# Relay_module.net
KiCad netlist of a schematic drawn in Altium Designer
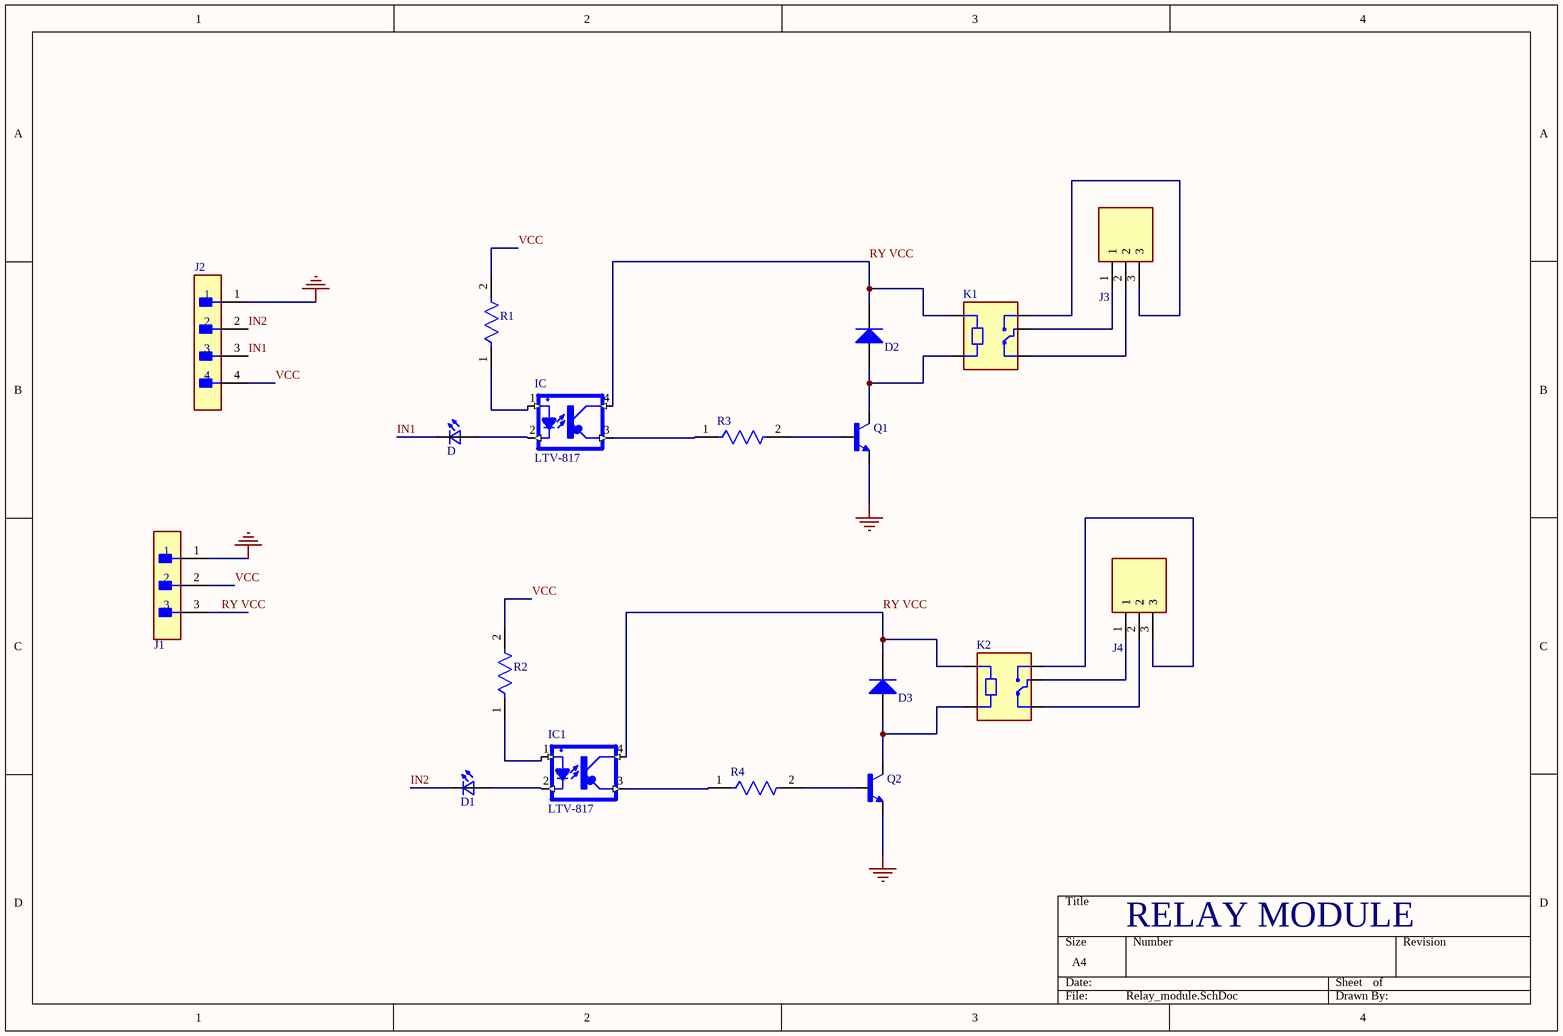
[diagram p0: Relay_module.SchDoc]

(export (version "E")
  (design (tool "Eeschema 10.0.6"))
  (components
    (comp (ref "D")
      (value "LTST-C193TBKT-5A")
      (footprint "0603")
      (description "Blue 470nm LED Indication - Discrete 2.8V 0603 _1608 Metric_")
      (fields (field (name "DIGI-KEY_PART_NUMBER") "160-1827-1-ND") (field (name "MF") "Lite-On Inc."))
      (libsource (lib "led") (part "LTST-C193TBKT-5A"))
    )
    (comp (ref "D1")
      (value "LTST-C193TBKT-5A")
      (footprint "0603")
      (description "Blue 470nm LED Indication - Discrete 2.8V 0603 _1608 Metric_")
      (fields (field (name "DIGI-KEY_PART_NUMBER") "160-1827-1-ND") (field (name "MF") "Lite-On Inc."))
      (libsource (lib "led") (part "LTST-C193TBKT-5A"))
    )
    (comp (ref "D2")
      (value "1N4003-T")
      (footprint "DIOD-DO-41-P-2_V")
      (description "1.0 A Rectifier, 15 pF, 200 V, -65 to 150 degC, 2-Pin DO-41 Plastic, RoHS, Tape and Reel")
      (fields (field (name "MANUFACTURER") "Diodes Inc"))
      (libsource (lib "Altium Content Vault") (part "DIOD-D-A1K2-2"))
    )
    (comp (ref "D3")
      (value "1N4003-T")
      (footprint "DIOD-DO-41-P-2_V")
      (description "1.0 A Rectifier, 15 pF, 200 V, -65 to 150 degC, 2-Pin DO-41 Plastic, RoHS, Tape and Reel")
      (fields (field (name "MANUFACTURER") "Diodes Inc"))
      (libsource (lib "Altium Content Vault") (part "DIOD-D-A1K2-2"))
    )
    (comp (ref "IC")
      (value "LTV-817")
      (footprint "DIP-4")
      (description "Optoisolator Transistor Output 5000Vrms 1 Channel 4-SMD")
      (fields (field (name "MF") "Lite-On Electronics"))
      (libsource (lib "SnapEDAsch") (part "LTV-817"))
    )
    (comp (ref "IC1")
      (value "LTV-817")
      (footprint "DIP-4")
      (description "Optoisolator Transistor Output 5000Vrms 1 Channel 4-SMD")
      (fields (field (name "MF") "Lite-On Electronics"))
      (libsource (lib "SnapEDAsch") (part "LTV-817"))
    )
    (comp (ref "J1")
      (value "22-05-3031")
      (footprint "FP-22-05-3031-MFG")
      (description "CONN HEADER R/A 3POS 2.54MM")
      (libsource (lib "Altium Content Vault") (part "0d3f023dd272f625e17a2be33dea85f"))
    )
    (comp (ref "J2")
      (value "22-05-3041")
      (footprint "FP-22-05-3041-MFG")
      (description "Connector Header Through Hole, Right Angle 4 position 0.100\" (2.54mm)")
      (fields (field (name "OCTOPART") "https://octopart.com/22-05-3041-molex-2579"))
      (libsource (lib "Altium Content Vault") (part "299a8cea1bdcbc3624fe62c390fa72c"))
    )
    (comp (ref "J3")
      (value "TB006-508-03BE")
      (footprint "CUI_TB006-508-03BE")
      (description "2~24 Poles, Screw Type, Horizontal, 5.08 Pitch, 26~14 (AWG), Terminal Block Connector")
      (fields (field (name "MF") "CUI Devices"))
      (libsource (lib "TB006-508-03BE") (part "TB006-508-03BE"))
    )
    (comp (ref "J4")
      (value "TB006-508-03BE")
      (footprint "CUI_TB006-508-03BE")
      (description "2~24 Poles, Screw Type, Horizontal, 5.08 Pitch, 26~14 (AWG), Terminal Block Connector")
      (fields (field (name "MF") "CUI Devices"))
      (libsource (lib "TB006-508-03BE") (part "TB006-508-03BE"))
    )
    (comp (ref "K1")
      (value "SRD-05VDC-SL-C")
      (footprint "RELAY_SRD-05VDC-SL-C")
      (fields (field (name "MF") "Songle Relay"))
      (libsource (lib "SRD-05VDC-SL-C") (part "SRD-05VDC-SL-C"))
    )
    (comp (ref "K2")
      (value "SRD-05VDC-SL-C")
      (footprint "RELAY_SRD-05VDC-SL-C")
      (fields (field (name "MF") "Songle Relay"))
      (libsource (lib "SRD-05VDC-SL-C") (part "SRD-05VDC-SL-C"))
    )
    (comp (ref "Q1")
      (value "BCW31*")
      (footprint "SOT23-BEC")
      (description "Bipolar (BJT) Transistor NPN General Purpose Amplifier Surface Mount")
      (fields (field (name "MF") "ON Semiconductor") (field (name "MP") "BCW31"))
      (libsource (lib "BCW31") (part "BCW31*"))
    )
    (comp (ref "Q2")
      (value "BCW31*")
      (footprint "SOT23-BEC")
      (description "Bipolar (BJT) Transistor NPN General Purpose Amplifier Surface Mount")
      (fields (field (name "MF") "ON Semiconductor") (field (name "MP") "BCW31"))
      (libsource (lib "BCW31") (part "BCW31*"))
    )
    (comp (ref "R1")
      (value "MRS25000C1000FRP00")
      (footprint "FP-MRS25-MFG")
      (fields (field (name "TOLERANCE") "1%"))
      (libsource (lib "Altium Content Vault") (part "1029c3af85768c4190bb7ad29bc67b5"))
    )
    (comp (ref "R2")
      (value "MRS25000C1000FRP00")
      (footprint "FP-MRS25-MFG")
      (fields (field (name "TOLERANCE") "1%"))
      (libsource (lib "Altium Content Vault") (part "1029c3af85768c4190bb7ad29bc67b5"))
    )
    (comp (ref "R3")
      (value "MRS25000C1000FRP00")
      (footprint "FP-MRS25-MFG")
      (fields (field (name "TOLERANCE") "1%"))
      (libsource (lib "Altium Content Vault") (part "1029c3af85768c4190bb7ad29bc67b5"))
    )
    (comp (ref "R4")
      (value "MRS25000C1000FRP00")
      (footprint "FP-MRS25-MFG")
      (fields (field (name "TOLERANCE") "1%"))
      (libsource (lib "Altium Content Vault") (part "1029c3af85768c4190bb7ad29bc67b5"))
    )
  )
  (nets
    (net (code "1") (name "/IN1") (class "Default")
      (node (ref "D") (pin "1") (pinfunction "K2_1") (pintype "passive"))
      (node (ref "J2") (pin "3") (pinfunction "3_3") (pintype "passive"))
    )
    (net (code "2") (name "/IN2") (class "Default")
      (node (ref "D1") (pin "1") (pinfunction "K2_1") (pintype "passive"))
      (node (ref "J2") (pin "2") (pinfunction "2_2") (pintype "passive"))
    )
    (net (code "3") (name "/RY VCC") (class "Default")
      (node (ref "D2") (pin "2") (pinfunction "K_2") (pintype "passive"))
      (node (ref "D3") (pin "2") (pinfunction "K_2") (pintype "passive"))
      (node (ref "IC") (pin "4") (pinfunction "4_4") (pintype "input"))
      (node (ref "IC1") (pin "4") (pinfunction "4_4") (pintype "input"))
      (node (ref "J1") (pin "3") (pinfunction "3_3") (pintype "passive"))
      (node (ref "K1") (pin "A1") (pinfunction "A1_A1") (pintype "passive"))
      (node (ref "K2") (pin "A1") (pinfunction "A1_A1") (pintype "passive"))
    )
    (net (code "4") (name "/VCC") (class "Default")
      (node (ref "J1") (pin "2") (pinfunction "2_2") (pintype "passive"))
      (node (ref "J2") (pin "4") (pinfunction "4_4") (pintype "passive"))
      (node (ref "R1") (pin "2") (pinfunction "2_2") (pintype "passive"))
      (node (ref "R2") (pin "2") (pinfunction "2_2") (pintype "passive"))
    )
    (net (code "5") (name "GND") (class "Default")
      (node (ref "J1") (pin "1") (pinfunction "1_1") (pintype "passive"))
      (node (ref "J2") (pin "1") (pinfunction "1_1") (pintype "passive"))
      (node (ref "Q1") (pin "E") (pinfunction "E_E") (pintype "passive"))
      (node (ref "Q2") (pin "E") (pinfunction "E_E") (pintype "passive"))
    )
    (net (code "6") (name "Net-(D-A2)") (class "Default")
      (node (ref "D") (pin "2") (pinfunction "A2_2") (pintype "passive"))
      (node (ref "IC") (pin "2") (pinfunction "2_2") (pintype "output"))
    )
    (net (code "7") (name "Net-(D1-A2)") (class "Default")
      (node (ref "D1") (pin "2") (pinfunction "A2_2") (pintype "passive"))
      (node (ref "IC1") (pin "2") (pinfunction "2_2") (pintype "output"))
    )
    (net (code "8") (name "Net-(D2-A)") (class "Default")
      (node (ref "D2") (pin "1") (pinfunction "A_1") (pintype "passive"))
      (node (ref "K1") (pin "A2") (pinfunction "A2_A2") (pintype "passive"))
      (node (ref "Q1") (pin "C") (pinfunction "C_C") (pintype "passive"))
    )
    (net (code "9") (name "Net-(D3-A)") (class "Default")
      (node (ref "D3") (pin "1") (pinfunction "A_1") (pintype "passive"))
      (node (ref "K2") (pin "A2") (pinfunction "A2_A2") (pintype "passive"))
      (node (ref "Q2") (pin "C") (pinfunction "C_C") (pintype "passive"))
    )
    (net (code "10") (name "Net-(IC-Pad1)") (class "Default")
      (node (ref "IC") (pin "1") (pinfunction "1_1") (pintype "input"))
      (node (ref "R1") (pin "1") (pinfunction "1_1") (pintype "passive"))
    )
    (net (code "11") (name "Net-(IC-Pad3)") (class "Default")
      (node (ref "IC") (pin "3") (pinfunction "3_3") (pintype "output"))
      (node (ref "R3") (pin "1") (pinfunction "1_1") (pintype "passive"))
    )
    (net (code "12") (name "Net-(IC1-Pad1)") (class "Default")
      (node (ref "IC1") (pin "1") (pinfunction "1_1") (pintype "input"))
      (node (ref "R2") (pin "1") (pinfunction "1_1") (pintype "passive"))
    )
    (net (code "13") (name "Net-(IC1-Pad3)") (class "Default")
      (node (ref "IC1") (pin "3") (pinfunction "3_3") (pintype "output"))
      (node (ref "R4") (pin "1") (pinfunction "1_1") (pintype "passive"))
    )
    (net (code "14") (name "Net-(J3-Pad1)") (class "Default")
      (node (ref "J3") (pin "1") (pinfunction "1_1") (pintype "passive"))
      (node (ref "K1") (pin "COM") (pinfunction "COM_COM") (pintype "passive"))
    )
    (net (code "15") (name "Net-(J3-Pad2)") (class "Default")
      (node (ref "J3") (pin "2") (pinfunction "2_2") (pintype "passive"))
      (node (ref "K1") (pin "NC") (pinfunction "NC_NC") (pintype "passive"))
    )
    (net (code "16") (name "Net-(J3-Pad3)") (class "Default")
      (node (ref "J3") (pin "3") (pinfunction "3_3") (pintype "passive"))
      (node (ref "K1") (pin "NO") (pinfunction "NO_NO") (pintype "passive"))
    )
    (net (code "17") (name "Net-(J4-Pad1)") (class "Default")
      (node (ref "J4") (pin "1") (pinfunction "1_1") (pintype "passive"))
      (node (ref "K2") (pin "COM") (pinfunction "COM_COM") (pintype "passive"))
    )
    (net (code "18") (name "Net-(J4-Pad2)") (class "Default")
      (node (ref "J4") (pin "2") (pinfunction "2_2") (pintype "passive"))
      (node (ref "K2") (pin "NC") (pinfunction "NC_NC") (pintype "passive"))
    )
    (net (code "19") (name "Net-(J4-Pad3)") (class "Default")
      (node (ref "J4") (pin "3") (pinfunction "3_3") (pintype "passive"))
      (node (ref "K2") (pin "NO") (pinfunction "NO_NO") (pintype "passive"))
    )
    (net (code "20") (name "Net-(Q1-PadB)") (class "Default")
      (node (ref "Q1") (pin "B") (pinfunction "B_B") (pintype "passive"))
      (node (ref "R3") (pin "2") (pinfunction "2_2") (pintype "passive"))
    )
    (net (code "21") (name "Net-(Q2-PadB)") (class "Default")
      (node (ref "Q2") (pin "B") (pinfunction "B_B") (pintype "passive"))
      (node (ref "R4") (pin "2") (pinfunction "2_2") (pintype "passive"))
    )
  )
)
